# SCH_PCB-Hacker-Card.net
KiCad netlist of a schematic drawn in EasyEDA
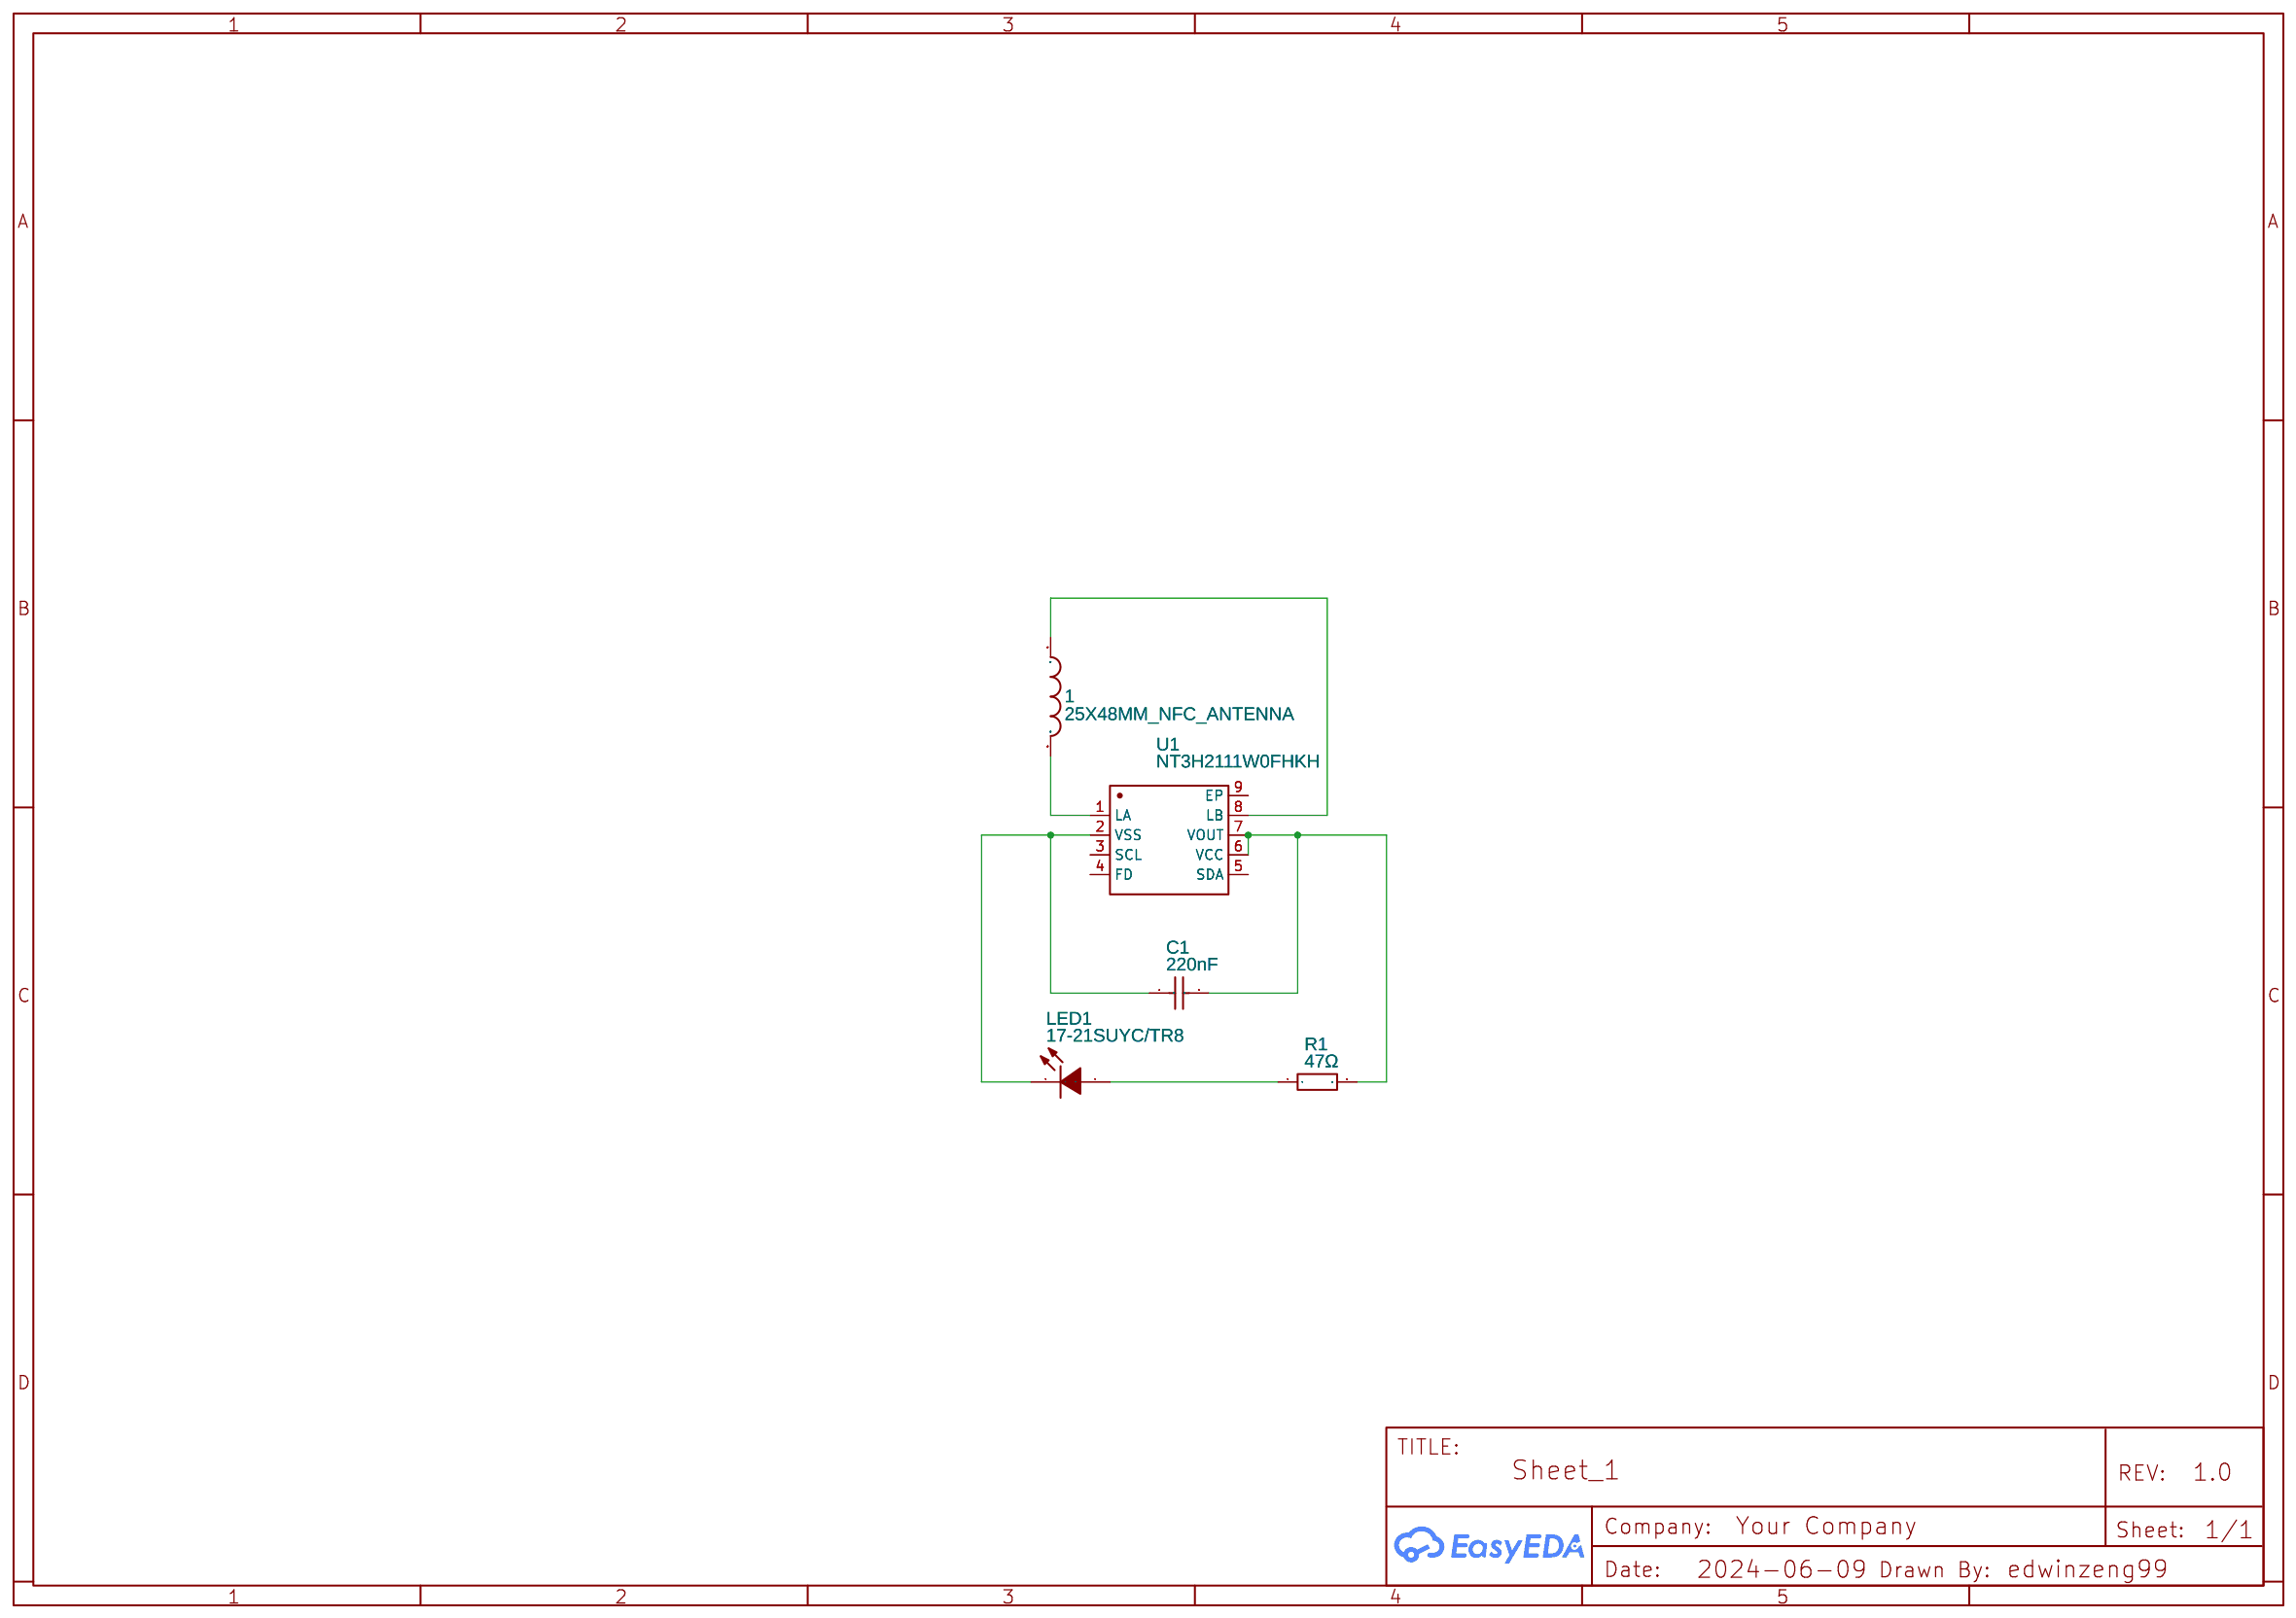
[diagram p0: schematic sheet]

(export (version "E")
  (design (tool "Eeschema 10.0.6"))
  (components
    (comp (ref "1") (value "25X48MM_NFC_ANTENNA") (libsource (lib "") (part "25X48MM_NFC_ANTENNA")))
    (comp (ref "C1")
      (value "220nF")
      (fields
        (field (name "Manufacturer Part") "CL10B224KA8NNNC")
        (field (name "Manufacturer") "SAMSUNG(三星)")
      )
      (libsource (lib "") (part "CL10B224KA8NNNC"))
    )
    (comp (ref "LED1")
      (value "17-21SUYC/TR8")
      (fields (field (name "Manufacturer Part") "KT-0805黄灯") (field (name "Manufacturer") "KENTO"))
      (libsource (lib "") (part "17-21SUYC/TR8"))
    )
    (comp (ref "R1")
      (value "47Ω")
      (fields
        (field (name "Manufacturer Part") "0603WAF470JT5E")
        (field (name "Manufacturer") "UNI-ROYAL(厚声)")
      )
      (libsource (lib "") (part "0603WAF470JT5E"))
    )
    (comp (ref "U1")
      (value "NT3H2111W0FHKH")
      (fields (field (name "Manufacturer") "NXP(恩智浦)"))
      (libsource (lib "") (part "NT3H2111W0FHKH"))
    )
  )
  (nets
    (net (code "1") (name "Net-(LED1-+)") (class "Default")
      (node (ref "LED1") (pin "1") (pinfunction "+_1") (pintype "unspecified"))
      (node (ref "R1") (pin "1") (pinfunction "1_1") (pintype "input"))
    )
    (net (code "2") (name "Net-(LED1--)") (class "Default")
      (node (ref "C1") (pin "1") (pinfunction "1_1") (pintype "input"))
      (node (ref "LED1") (pin "2") (pinfunction "-_2") (pintype "unspecified"))
      (node (ref "U1") (pin "2") (pinfunction "VSS_2") (pintype "unspecified"))
    )
    (net (code "3") (name "Net-(U1-LA)") (class "Default")
      (node (ref "1") (pin "P$2") (pinfunction "P$2_P$2") (pintype "bidirectional"))
      (node (ref "U1") (pin "1") (pinfunction "LA_1") (pintype "unspecified"))
    )
    (net (code "4") (name "Net-(U1-LB)") (class "Default")
      (node (ref "1") (pin "P$1") (pinfunction "P$1_P$1") (pintype "bidirectional"))
      (node (ref "U1") (pin "8") (pinfunction "LB_8") (pintype "unspecified"))
    )
    (net (code "5") (name "Net-(U1-VCC)") (class "Default")
      (node (ref "C1") (pin "2") (pinfunction "2_2") (pintype "input"))
      (node (ref "R1") (pin "2") (pinfunction "2_2") (pintype "input"))
      (node (ref "U1") (pin "6") (pinfunction "VCC_6") (pintype "unspecified"))
      (node (ref "U1") (pin "7") (pinfunction "VOUT_7") (pintype "unspecified"))
    )
    (net (code "6") (name "unconnected-(U1-EP-Pad9)") (class "Default")
      (node (ref "U1") (pin "9") (pinfunction "EP_9") (pintype "unspecified"))
    )
    (net (code "7") (name "unconnected-(U1-FD-Pad4)") (class "Default")
      (node (ref "U1") (pin "4") (pinfunction "FD_4") (pintype "unspecified"))
    )
    (net (code "8") (name "unconnected-(U1-SCL-Pad3)") (class "Default")
      (node (ref "U1") (pin "3") (pinfunction "SCL_3") (pintype "unspecified"))
    )
    (net (code "9") (name "unconnected-(U1-SDA-Pad5)") (class "Default")
      (node (ref "U1") (pin "5") (pinfunction "SDA_5") (pintype "unspecified"))
    )
  )
)
